# Portier.net
KiCad netlist of a schematic drawn in Altium Designer
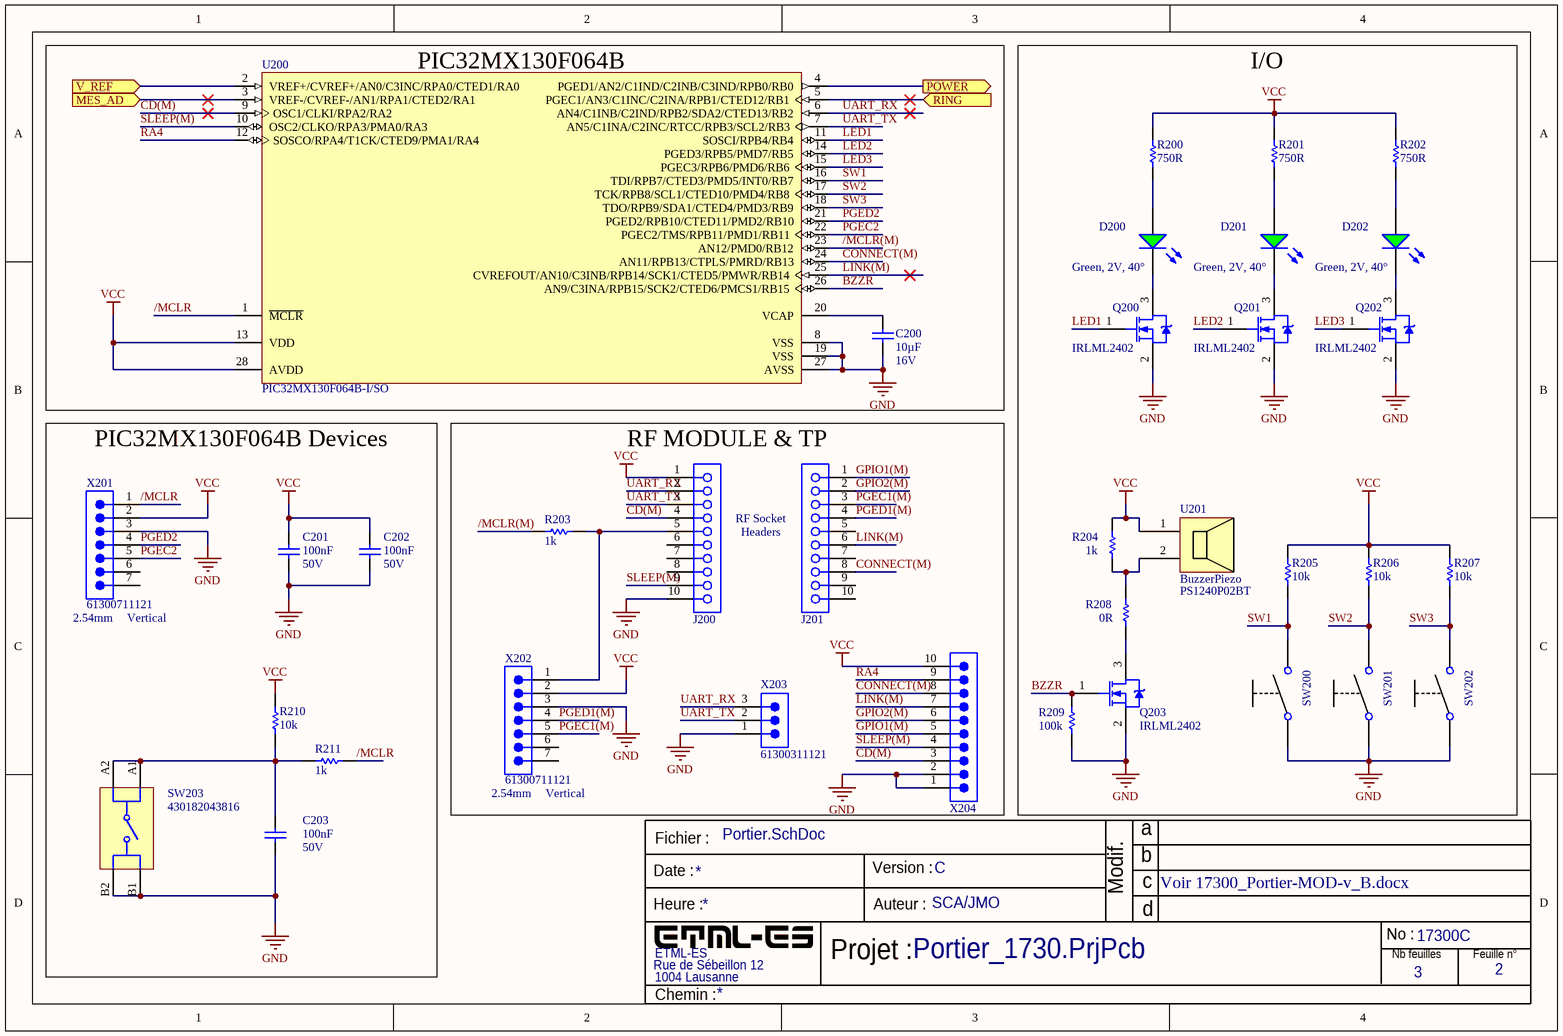
[diagram p0: Portier.SchDoc]

(export (version "E")
  (design (tool "Eeschema 10.0.6"))
  (components
    (comp (ref "C200")
      (value "10µF")
      (footprint "WCAP-CSGP_0805_L2W1.25H1.25")
      (description "WCAP-CSGP Multilayer Ceramic Chip Capacitor, General Purpose, size 0805, X5R, 10µF, 16VDC")
      (fields
        (field (name "MANUFACTURER PART NUMBER") "885012107014")
        (field (name "MANUFACTURER") "Wurth Elektronik")
        (field (name "RATED VOLTAGE (DC)") "16V")
      )
      (libsource (lib "Altium_WCAP-CSGP (rev22f)") (part "885012107014"))
    )
    (comp (ref "C201")
      (value "100nF")
      (footprint "WCAP-CSGP_0805_L2W1.25H0.8_Reflow")
      (description "WCAP-CSGP Multilayer Ceramic Chip Capacitor, General Purpose, size 0805, X7R, 100nF, 50VDC")
      (fields
        (field (name "MANUFACTURER") "Wurth Elektronik")
        (field (name "MANUFACTURER PART NUMBER") "885012207098")
        (field (name "RATED VOLTAGE (DC)") "50V")
      )
      (libsource (lib "Altium_WCAP-CSGP (rev22f)") (part "885012207098"))
    )
    (comp (ref "C202")
      (value "100nF")
      (footprint "WCAP-CSGP_0805_L2W1.25H0.8_Reflow")
      (description "WCAP-CSGP Multilayer Ceramic Chip Capacitor, General Purpose, size 0805, X7R, 100nF, 50VDC")
      (fields
        (field (name "MANUFACTURER") "Wurth Elektronik")
        (field (name "MANUFACTURER PART NUMBER") "885012207098")
        (field (name "RATED VOLTAGE (DC)") "50V")
      )
      (libsource (lib "Altium_WCAP-CSGP (rev22f)") (part "885012207098"))
    )
    (comp (ref "C203")
      (value "100nF")
      (footprint "WCAP-CSGP_0805_L2W1.25H0.8_Reflow")
      (description "WCAP-CSGP Multilayer Ceramic Chip Capacitor, General Purpose, size 0805, X7R, 100nF, 50VDC")
      (fields
        (field (name "MANUFACTURER") "Wurth Elektronik")
        (field (name "MANUFACTURER PART NUMBER") "885012207098")
        (field (name "RATED VOLTAGE (DC)") "50V")
      )
      (libsource (lib "Altium_WCAP-CSGP (rev22f)") (part "885012207098"))
    )
    (comp (ref "D200")
      (value "Green, 2V, 40°")
      (footprint "WL-SMCW_0805_150080xx75000")
      (description "WL-SMCW Mono-color Chip LED Waterclear, size 0805, Bright Green, 2V, 140°")
      (fields
        (field (name "MANUFACTURER PART NUMBER") "150080VS75000")
        (field (name "MANUFACTURER") "Wurth Elektronik")
      )
      (libsource (lib "Altium_WL-SMCW (rev22d)") (part "150080VS75000"))
    )
    (comp (ref "D201")
      (value "Green, 2V, 40°")
      (footprint "WL-SMCW_0805_150080xx75000")
      (description "WL-SMCW Mono-color Chip LED Waterclear, size 0805, Bright Green, 2V, 140°")
      (fields
        (field (name "MANUFACTURER PART NUMBER") "150080VS75000")
        (field (name "MANUFACTURER") "Wurth Elektronik")
      )
      (libsource (lib "Altium_WL-SMCW (rev22d)") (part "150080VS75000"))
    )
    (comp (ref "D202")
      (value "Green, 2V, 40°")
      (footprint "WL-SMCW_0805_150080xx75000")
      (description "WL-SMCW Mono-color Chip LED Waterclear, size 0805, Bright Green, 2V, 140°")
      (fields
        (field (name "MANUFACTURER PART NUMBER") "150080VS75000")
        (field (name "MANUFACTURER") "Wurth Elektronik")
      )
      (libsource (lib "Altium_WL-SMCW (rev22d)") (part "150080VS75000"))
    )
    (comp (ref "J200")
      (value "62001011821")
      (footprint "62001011821")
      (description "WR-PHD Socket Header, THT, Vertical, pitch 2mm, 1 Row, 10P")
      (fields (field (name "MANUFACTURER") "Wurth Elektronik"))
      (libsource (lib "Altium_WR-PHD (rev22b)") (part "62001011821"))
    )
    (comp (ref "J201")
      (value "62001011821")
      (footprint "62001011821")
      (description "WR-PHD Socket Header, THT, Vertical, pitch 2mm, 1 Row, 10P")
      (fields (field (name "MANUFACTURER") "Wurth Elektronik"))
      (libsource (lib "Altium_WR-PHD (rev22b)") (part "62001011821"))
    )
    (comp (ref "Q200")
      (value "IRLML2402")
      (footprint "INTR-IRLML2402TRPBF-3_V")
      (description "HEXFET(R) Power MOSFET, N-Channel, 20 V, 1.2 A, 3-Pin SOT-23, RoHS, Tape and Reel")
      (fields
        (field (name "MANUFACTURER") "Infineon Technologies")
        (field (name "PARTNUMBER") "IRLML2402TRBF")
      )
      (libsource (lib "Altium Content Vault") (part "CMP-2000-05155-1"))
    )
    (comp (ref "Q201")
      (value "IRLML2402")
      (footprint "INTR-IRLML2402TRPBF-3_V")
      (description "HEXFET(R) Power MOSFET, N-Channel, 20 V, 1.2 A, 3-Pin SOT-23, RoHS, Tape and Reel")
      (fields
        (field (name "MANUFACTURER") "Infineon Technologies")
        (field (name "PARTNUMBER") "IRLML2402TRBF")
      )
      (libsource (lib "Altium Content Vault") (part "CMP-2000-05155-1"))
    )
    (comp (ref "Q202")
      (value "IRLML2402")
      (footprint "INTR-IRLML2402TRPBF-3_V")
      (description "HEXFET(R) Power MOSFET, N-Channel, 20 V, 1.2 A, 3-Pin SOT-23, RoHS, Tape and Reel")
      (fields
        (field (name "MANUFACTURER") "Infineon Technologies")
        (field (name "PARTNUMBER") "IRLML2402TRBF")
      )
      (libsource (lib "Altium Content Vault") (part "CMP-2000-05155-1"))
    )
    (comp (ref "Q203")
      (value "IRLML2402")
      (footprint "INTR-IRLML2402TRPBF-3_V")
      (description "HEXFET(R) Power MOSFET, N-Channel, 20 V, 1.2 A, 3-Pin SOT-23, RoHS, Tape and Reel")
      (fields
        (field (name "MANUFACTURER") "Infineon Technologies")
        (field (name "PARTNUMBER") "IRLML2402TRBF")
      )
      (libsource (lib "Altium Content Vault") (part "CMP-2000-05155-1"))
    )
    (comp (ref "R200")
      (value "750R")
      (footprint "RESC2013X50X30NL20T20")
      (description "750 ohm, 0.125W, 1%., 0805")
      (fields (field (name "MANUFACTURER") "Vishay Dale") (field (name "PART NUMBER") "CRCW0805750KFKEA"))
      (libsource (lib "Altium Content Vault") (part "RES"))
    )
    (comp (ref "R201")
      (value "750R")
      (footprint "RESC2013X50X30NL20T20")
      (description "750 ohm, 0.125W, 1%., 0805")
      (fields (field (name "MANUFACTURER") "Vishay Dale") (field (name "PART NUMBER") "CRCW0805750KFKEA"))
      (libsource (lib "Altium Content Vault") (part "RES"))
    )
    (comp (ref "R202")
      (value "750R")
      (footprint "RESC2013X50X30NL20T20")
      (description "750 ohm, 0.125W, 1%., 0805")
      (fields (field (name "MANUFACTURER") "Vishay Dale") (field (name "PART NUMBER") "CRCW0805750KFKEA"))
      (libsource (lib "Altium Content Vault") (part "RES"))
    )
    (comp (ref "R203")
      (value "1k")
      (footprint "RESC2013X50X30ML20T20")
      (fields (field (name "PART NUMBER") "CRCW08051K00FKEA") (field (name "MANUFACTURER") "Vishay Dale"))
      (libsource (lib "Altium Content Vault") (part "RES"))
    )
    (comp (ref "R204")
      (value "1k")
      (footprint "RESC2013X50X30ML20T20")
      (fields (field (name "PART NUMBER") "CRCW08051K00FKEA") (field (name "MANUFACTURER") "Vishay Dale"))
      (libsource (lib "Altium Content Vault") (part "RES"))
    )
    (comp (ref "R205")
      (value "10k")
      (footprint "RESC2013X60X35NL10T20")
      (description "Chip Resistor, 10 KOhm, +/- 1%, 0.125 W, -55 to 155 degC, 0805 (2012 Metric), RoHS, Tape and Reel")
      (libsource (lib "Altium Content Vault") (part "RES-2"))
    )
    (comp (ref "R206")
      (value "10k")
      (footprint "RESC2013X60X35NL10T20")
      (description "Chip Resistor, 10 KOhm, +/- 1%, 0.125 W, -55 to 155 degC, 0805 (2012 Metric), RoHS, Tape and Reel")
      (libsource (lib "Altium Content Vault") (part "RES-2"))
    )
    (comp (ref "R207")
      (value "10k")
      (footprint "RESC2013X60X35NL10T20")
      (description "Chip Resistor, 10 KOhm, +/- 1%, 0.125 W, -55 to 155 degC, 0805 (2012 Metric), RoHS, Tape and Reel")
      (libsource (lib "Altium Content Vault") (part "RES-2"))
    )
    (comp (ref "R208")
      (value "0R")
      (footprint "RESC2013X60X35ML10T20")
      (description "Chip Resistor, 0 Ohm, +/- 5%, 125 mW, -55 to 155 degC, 0805 (2012 Metric), RoHS, Tape and Reel")
      (fields (field (name "MANUFACTURER") "Yageo"))
      (libsource (lib "Altium Content Vault") (part "RES-2"))
    )
    (comp (ref "R209")
      (value "100k")
      (footprint "RESC2013X70X40ML20T20")
      (description "100 kOhms ±1% 0.125W, 1/8W Chip Resistor 0805 (2012 Metric) Automotive AEC-Q200 Thick Film")
      (fields (field (name "PART NUMBER") "ERJ-6ENF1003V") (field (name "MANUFACTURER") "Panasonic"))
      (libsource (lib "Altium Content Vault") (part "RES"))
    )
    (comp (ref "R210")
      (value "10k")
      (footprint "RESC2013X60X35NL10T20")
      (description "Chip Resistor, 10 KOhm, +/- 1%, 0.125 W, -55 to 155 degC, 0805 (2012 Metric), RoHS, Tape and Reel")
      (libsource (lib "Altium Content Vault") (part "RES-2"))
    )
    (comp (ref "R211")
      (value "1k")
      (footprint "RESC2013X50X30ML20T20")
      (fields (field (name "PART NUMBER") "CRCW08051K00FKEA") (field (name "MANUFACTURER") "Vishay Dale"))
      (libsource (lib "Altium Content Vault") (part "RES"))
    )
    (comp (ref "SW200")
      (value "Tact-sw 1241.1022")
      (footprint "Tact-sw 1241.1022")
      (libsource (lib "Schurter-switches") (part "Tact-sw 1241.1022"))
    )
    (comp (ref "SW201")
      (value "Tact-sw 1241.1022")
      (footprint "Tact-sw 1241.1022")
      (libsource (lib "Schurter-switches") (part "Tact-sw 1241.1022"))
    )
    (comp (ref "SW202")
      (value "Tact-sw 1241.1022")
      (footprint "Tact-sw 1241.1022")
      (libsource (lib "Schurter-switches") (part "Tact-sw 1241.1022"))
    )
    (comp (ref "SW203")
      (value "430182043816")
      (footprint "WS-TASV_L6W6H4.3_4301x20438x6")
      (description "WS-TASV SMT Tact Switch, L6 x W6 x H4.3mm, 160g, SPST-NO, 12V, 50mA")
      (fields (field (name "MANUFACTURER") "Wurth Elektronik"))
      (libsource (lib "Altium_WS-TASV (rev22c)") (part "430182043816"))
    )
    (comp (ref "U200")
      (value "PIC32MX130F064B-I/SO")
      (footprint "MCHP-SOIC-SO28_M")
      (fields (field (name "MANUFACTURER") "Microchip"))
      (libsource (lib "Altium Content Vault") (part "MCHP-PIC32MX1X0FXXXB-28"))
    )
    (comp (ref "U201")
      (value "BuzzerPiezo")
      (footprint "Buzzer")
      (description "Buzzer 12mm piezo")
      (fields
        (field (name "MANUFACTURER") "TDK Corporation")
        (field (name "PARTNUMBER") "PS1240P02BT")
        (field (name "ALTIUM_VALUE") "PS1240P02BT")
      )
      (libsource (lib "CircuitOUT") (part "BZR"))
    )
    (comp (ref "X201")
      (value "61300711121")
      (footprint "61300711121")
      (description "WR-PHD Pin Header, THT, Vertical, pitch 2.54mm, 1 Row, 7P")
      (fields
        (field (name "MANUFACTURER") "Wurth Elektronik")
        (field (name "ORIENTATION") "Vertical")
        (field (name "PITCH") "2.54mm")
      )
      (libsource (lib "Altium_WR-PHD (rev22b)") (part "61300711121"))
    )
    (comp (ref "X202")
      (value "61300711121")
      (footprint "61300711121")
      (description "WR-PHD Pin Header, THT, Vertical, pitch 2.54mm, 1 Row, 7P")
      (fields
        (field (name "MANUFACTURER") "Wurth Elektronik")
        (field (name "ORIENTATION") "Vertical")
        (field (name "PITCH") "2.54mm")
      )
      (libsource (lib "Altium_WR-PHD (rev22b)") (part "61300711121"))
    )
    (comp (ref "X203")
      (value "61300311121")
      (footprint "61300311121")
      (description "WR-PHD Pin Header, THT, Vertical, pitch 2.54mm, 1 Row, 3P")
      (fields (field (name "MANUFACTURER") "Wurth Elektronik"))
      (libsource (lib "Altium_WR-PHD (rev22b)") (part "61300311121"))
    )
    (comp (ref "X204")
      (value "61301011121")
      (footprint "61301011121")
      (description "WR-PHD Pin Header, THT, Vertical, pitch 2.54mm, 1 Row, 10P")
      (fields (field (name "MANUFACTURER") "Wurth Elektronik"))
      (libsource (lib "Altium_WR-PHD (rev22b)") (part "61301011121"))
    )
  )
  (nets
    (net (code "1") (name "/BZZR") (class "Default")
      (node (ref "Q203") (pin "1") (pinfunction "G_1") (pintype "passive"))
      (node (ref "R209") (pin "2") (pinfunction "2_2") (pintype "passive"))
      (node (ref "U200") (pin "26") (pinfunction "AN9/C3INA/RPB15/SCK2/CTED6/PMCS1/RB15_26") (pintype "bidirectional"))
    )
    (net (code "2") (name "/CD(M)") (class "Default")
      (node (ref "J200") (pin "4") (pinfunction "4_4") (pintype "passive"))
      (node (ref "U200") (pin "9") (pinfunction "OSC1/CLKI/RPA2/RA2_9") (pintype "input"))
      (node (ref "X204") (pin "3") (pinfunction "3_3") (pintype "passive"))
    )
    (net (code "3") (name "/CONNECT(M)") (class "Default")
      (node (ref "J201") (pin "8") (pinfunction "8_8") (pintype "passive"))
      (node (ref "U200") (pin "24") (pinfunction "AN11/RPB13/CTPLS/PMRD/RB13_24") (pintype "bidirectional"))
      (node (ref "X204") (pin "8") (pinfunction "8_8") (pintype "passive"))
    )
    (net (code "4") (name "/GPIO1(M)") (class "Default")
      (node (ref "J201") (pin "1") (pinfunction "1_1") (pintype "passive"))
      (node (ref "X204") (pin "5") (pinfunction "5_5") (pintype "passive"))
    )
    (net (code "5") (name "/GPIO2(M)") (class "Default")
      (node (ref "J201") (pin "2") (pinfunction "2_2") (pintype "passive"))
      (node (ref "X204") (pin "6") (pinfunction "6_6") (pintype "passive"))
    )
    (net (code "6") (name "/LED1") (class "Default")
      (node (ref "Q200") (pin "1") (pinfunction "G_1") (pintype "passive"))
      (node (ref "U200") (pin "11") (pinfunction "SOSCI/RPB4/RB4_11") (pintype "bidirectional"))
    )
    (net (code "7") (name "/LED2") (class "Default")
      (node (ref "Q201") (pin "1") (pinfunction "G_1") (pintype "passive"))
      (node (ref "U200") (pin "14") (pinfunction "PGED3/RPB5/PMD7/RB5_14") (pintype "bidirectional"))
    )
    (net (code "8") (name "/LED3") (class "Default")
      (node (ref "Q202") (pin "1") (pinfunction "G_1") (pintype "passive"))
      (node (ref "U200") (pin "15") (pinfunction "PGEC3/RPB6/PMD6/RB6_15") (pintype "bidirectional"))
    )
    (net (code "9") (name "/LINK(M)") (class "Default")
      (node (ref "J201") (pin "6") (pinfunction "6_6") (pintype "passive"))
      (node (ref "U200") (pin "25") (pinfunction "CVREFOUT/AN10/C3INB/RPB14/SCK1/CTED5/PMWR/RB14_25") (pintype "input"))
      (node (ref "X204") (pin "7") (pinfunction "7_7") (pintype "passive"))
    )
    (net (code "10") (name "/MES_AD") (class "Default")
      (node (ref "U200") (pin "3") (pinfunction "VREF-/CVREF-/AN1/RPA1/CTED2/RA1_3") (pintype "input"))
    )
    (net (code "11") (name "/PGEC1(M)") (class "Default")
      (node (ref "J201") (pin "3") (pinfunction "3_3") (pintype "passive"))
      (node (ref "X202") (pin "5") (pinfunction "5_5") (pintype "passive"))
    )
    (net (code "12") (name "/PGEC2") (class "Default")
      (node (ref "U200") (pin "22") (pinfunction "PGEC2/TMS/RPB11/PMD1/RB11_22") (pintype "bidirectional"))
      (node (ref "X201") (pin "5") (pinfunction "5_5") (pintype "passive"))
    )
    (net (code "13") (name "/PGED1(M)") (class "Default")
      (node (ref "J201") (pin "4") (pinfunction "4_4") (pintype "passive"))
      (node (ref "X202") (pin "4") (pinfunction "4_4") (pintype "passive"))
    )
    (net (code "14") (name "/PGED2") (class "Default")
      (node (ref "U200") (pin "21") (pinfunction "PGED2/RPB10/CTED11/PMD2/RB10_21") (pintype "bidirectional"))
      (node (ref "X201") (pin "4") (pinfunction "4_4") (pintype "passive"))
    )
    (net (code "15") (name "/POWER") (class "Default")
      (node (ref "U200") (pin "4") (pinfunction "PGED1/AN2/C1IND/C2INB/C3IND/RPB0/RB0_4") (pintype "output"))
    )
    (net (code "16") (name "/RA4") (class "Default")
      (node (ref "U200") (pin "12") (pinfunction "SOSCO/RPA4/T1CK/CTED9/PMA1/RA4_12") (pintype "bidirectional"))
      (node (ref "X204") (pin "9") (pinfunction "9_9") (pintype "passive"))
    )
    (net (code "17") (name "/RING") (class "Default")
      (node (ref "U200") (pin "5") (pinfunction "PGEC1/AN3/C1INC/C2INA/RPB1/CTED12/RB1_5") (pintype "input"))
    )
    (net (code "18") (name "/SLEEP(M)") (class "Default")
      (node (ref "J200") (pin "9") (pinfunction "9_9") (pintype "passive"))
      (node (ref "U200") (pin "10") (pinfunction "OSC2/CLKO/RPA3/PMA0/RA3_10") (pintype "bidirectional"))
      (node (ref "X204") (pin "4") (pinfunction "4_4") (pintype "passive"))
    )
    (net (code "19") (name "/SW1") (class "Default")
      (node (ref "R205") (pin "1") (pinfunction "1_1") (pintype "passive"))
      (node (ref "SW200") (pin "2") (pinfunction "2_2") (pintype "passive"))
      (node (ref "U200") (pin "16") (pinfunction "TDI/RPB7/CTED3/PMD5/INT0/RB7_16") (pintype "bidirectional"))
    )
    (net (code "20") (name "/SW2") (class "Default")
      (node (ref "R206") (pin "1") (pinfunction "1_1") (pintype "passive"))
      (node (ref "SW201") (pin "2") (pinfunction "2_2") (pintype "passive"))
      (node (ref "U200") (pin "17") (pinfunction "TCK/RPB8/SCL1/CTED10/PMD4/RB8_17") (pintype "bidirectional"))
    )
    (net (code "21") (name "/SW3") (class "Default")
      (node (ref "R207") (pin "1") (pinfunction "1_1") (pintype "passive"))
      (node (ref "SW202") (pin "2") (pinfunction "2_2") (pintype "passive"))
      (node (ref "U200") (pin "18") (pinfunction "TDO/RPB9/SDA1/CTED4/PMD3/RB9_18") (pintype "bidirectional"))
    )
    (net (code "22") (name "/UART_RX") (class "Default")
      (node (ref "J200") (pin "2") (pinfunction "2_2") (pintype "passive"))
      (node (ref "U200") (pin "6") (pinfunction "AN4/C1INB/C2IND/RPB2/SDA2/CTED13/RB2_6") (pintype "input"))
      (node (ref "X203") (pin "3") (pinfunction "3_3") (pintype "passive"))
    )
    (net (code "23") (name "/UART_TX") (class "Default")
      (node (ref "J200") (pin "3") (pinfunction "3_3") (pintype "passive"))
      (node (ref "U200") (pin "7") (pinfunction "AN5/C1INA/C2INC/RTCC/RPB3/SCL2/RB3_7") (pintype "output"))
      (node (ref "X203") (pin "2") (pinfunction "2_2") (pintype "passive"))
    )
    (net (code "24") (name "/V_REF") (class "Default")
      (node (ref "U200") (pin "2") (pinfunction "VREF+/CVREF+/AN0/C3INC/RPA0/CTED1/RA0_2") (pintype "input"))
    )
    (net (code "25") (name "/{slash}MCLR") (class "Default")
      (node (ref "R211") (pin "2") (pinfunction "2_2") (pintype "passive"))
      (node (ref "U200") (pin "1") (pinfunction "~{MCLR}_1") (pintype "passive"))
      (node (ref "X201") (pin "1") (pinfunction "1_1") (pintype "passive"))
    )
    (net (code "26") (name "/{slash}MCLR(M)") (class "Default")
      (node (ref "R203") (pin "2") (pinfunction "2_2") (pintype "passive"))
      (node (ref "U200") (pin "23") (pinfunction "AN12/PMD0/RB12_23") (pintype "bidirectional"))
    )
    (net (code "27") (name "GND") (class "Default")
      (node (ref "C200") (pin "2") (pinfunction "2_2") (pintype "passive"))
      (node (ref "C201") (pin "1") (pinfunction "1_1") (pintype "passive"))
      (node (ref "C202") (pin "1") (pinfunction "1_1") (pintype "passive"))
      (node (ref "C203") (pin "1") (pinfunction "1_1") (pintype "passive"))
      (node (ref "J200") (pin "10") (pinfunction "10_10") (pintype "passive"))
      (node (ref "Q200") (pin "2") (pinfunction "S_2") (pintype "passive"))
      (node (ref "Q201") (pin "2") (pinfunction "S_2") (pintype "passive"))
      (node (ref "Q202") (pin "2") (pinfunction "S_2") (pintype "passive"))
      (node (ref "Q203") (pin "2") (pinfunction "S_2") (pintype "passive"))
      (node (ref "R209") (pin "1") (pinfunction "1_1") (pintype "passive"))
      (node (ref "SW200") (pin "1") (pinfunction "1_1") (pintype "passive"))
      (node (ref "SW201") (pin "1") (pinfunction "1_1") (pintype "passive"))
      (node (ref "SW202") (pin "1") (pinfunction "1_1") (pintype "passive"))
      (node (ref "SW203") (pin "B1") (pinfunction "B1_B1") (pintype "passive"))
      (node (ref "SW203") (pin "B2") (pinfunction "B2_B2") (pintype "passive"))
      (node (ref "U200") (pin "19") (pinfunction "VSS_19") (pintype "power_in"))
      (node (ref "U200") (pin "27") (pinfunction "AVSS_27") (pintype "power_in"))
      (node (ref "U200") (pin "8") (pinfunction "VSS_8") (pintype "power_in"))
      (node (ref "X201") (pin "3") (pinfunction "3_3") (pintype "passive"))
      (node (ref "X202") (pin "3") (pinfunction "3_3") (pintype "passive"))
      (node (ref "X203") (pin "1") (pinfunction "1_1") (pintype "passive"))
      (node (ref "X204") (pin "1") (pinfunction "1_1") (pintype "passive"))
      (node (ref "X204") (pin "2") (pinfunction "2_2") (pintype "passive"))
    )
    (net (code "28") (name "Net-(C203-Pad2)") (class "Default")
      (node (ref "C203") (pin "2") (pinfunction "2_2") (pintype "passive"))
      (node (ref "R210") (pin "2") (pinfunction "2_2") (pintype "passive"))
      (node (ref "R211") (pin "1") (pinfunction "1_1") (pintype "passive"))
      (node (ref "SW203") (pin "A1") (pinfunction "A1_A1") (pintype "passive"))
      (node (ref "SW203") (pin "A2") (pinfunction "A2_A2") (pintype "passive"))
    )
    (net (code "29") (name "Net-(D200-A)") (class "Default")
      (node (ref "D200") (pin "2") (pinfunction "A_2") (pintype "passive"))
      (node (ref "R200") (pin "2") (pinfunction "2_2") (pintype "passive"))
    )
    (net (code "30") (name "Net-(D200-K)") (class "Default")
      (node (ref "D200") (pin "1") (pinfunction "K_1") (pintype "passive"))
      (node (ref "Q200") (pin "3") (pinfunction "D_3") (pintype "passive"))
    )
    (net (code "31") (name "Net-(D201-A)") (class "Default")
      (node (ref "D201") (pin "2") (pinfunction "A_2") (pintype "passive"))
      (node (ref "R201") (pin "2") (pinfunction "2_2") (pintype "passive"))
    )
    (net (code "32") (name "Net-(D201-K)") (class "Default")
      (node (ref "D201") (pin "1") (pinfunction "K_1") (pintype "passive"))
      (node (ref "Q201") (pin "3") (pinfunction "D_3") (pintype "passive"))
    )
    (net (code "33") (name "Net-(D202-A)") (class "Default")
      (node (ref "D202") (pin "2") (pinfunction "A_2") (pintype "passive"))
      (node (ref "R202") (pin "1") (pinfunction "1_1") (pintype "passive"))
    )
    (net (code "34") (name "Net-(D202-K)") (class "Default")
      (node (ref "D202") (pin "1") (pinfunction "K_1") (pintype "passive"))
      (node (ref "Q202") (pin "3") (pinfunction "D_3") (pintype "passive"))
    )
    (net (code "35") (name "Net-(J200-Pad5)") (class "Default")
      (node (ref "J200") (pin "5") (pinfunction "5_5") (pintype "passive"))
      (node (ref "R203") (pin "1") (pinfunction "1_1") (pintype "passive"))
      (node (ref "X202") (pin "1") (pinfunction "1_1") (pintype "passive"))
    )
    (net (code "36") (name "Net-(Q203-D)") (class "Default")
      (node (ref "Q203") (pin "3") (pinfunction "D_3") (pintype "passive"))
      (node (ref "R208") (pin "1") (pinfunction "1_1") (pintype "passive"))
    )
    (net (code "37") (name "Net-(R204-Pad1)") (class "Default")
      (node (ref "R204") (pin "1") (pinfunction "1_1") (pintype "passive"))
      (node (ref "R208") (pin "2") (pinfunction "2_2") (pintype "passive"))
      (node (ref "U201") (pin "2") (pintype "passive"))
    )
    (net (code "38") (name "Net-(U200-VCAP)") (class "Default")
      (node (ref "C200") (pin "1") (pinfunction "1_1") (pintype "passive"))
      (node (ref "U200") (pin "20") (pinfunction "VCAP_20") (pintype "passive"))
    )
    (net (code "39") (name "VCC") (class "Default")
      (node (ref "C201") (pin "2") (pinfunction "2_2") (pintype "passive"))
      (node (ref "C202") (pin "2") (pinfunction "2_2") (pintype "passive"))
      (node (ref "J200") (pin "1") (pinfunction "1_1") (pintype "passive"))
      (node (ref "R200") (pin "1") (pinfunction "1_1") (pintype "passive"))
      (node (ref "R201") (pin "1") (pinfunction "1_1") (pintype "passive"))
      (node (ref "R202") (pin "2") (pinfunction "2_2") (pintype "passive"))
      (node (ref "R204") (pin "2") (pinfunction "2_2") (pintype "passive"))
      (node (ref "R205") (pin "2") (pinfunction "2_2") (pintype "passive"))
      (node (ref "R206") (pin "2") (pinfunction "2_2") (pintype "passive"))
      (node (ref "R207") (pin "2") (pinfunction "2_2") (pintype "passive"))
      (node (ref "R210") (pin "1") (pinfunction "1_1") (pintype "passive"))
      (node (ref "U200") (pin "13") (pinfunction "VDD_13") (pintype "power_in"))
      (node (ref "U200") (pin "28") (pinfunction "AVDD_28") (pintype "power_in"))
      (node (ref "U201") (pin "1") (pintype "passive"))
      (node (ref "X201") (pin "2") (pinfunction "2_2") (pintype "passive"))
      (node (ref "X202") (pin "2") (pinfunction "2_2") (pintype "passive"))
      (node (ref "X204") (pin "10") (pinfunction "10_10") (pintype "passive"))
    )
    (net (code "40") (name "unconnected-(J200-Pad6)") (class "Default")
      (node (ref "J200") (pin "6") (pinfunction "6_6") (pintype "passive"))
    )
    (net (code "41") (name "unconnected-(J200-Pad7)") (class "Default")
      (node (ref "J200") (pin "7") (pinfunction "7_7") (pintype "passive"))
    )
    (net (code "42") (name "unconnected-(J200-Pad8)") (class "Default")
      (node (ref "J200") (pin "8") (pinfunction "8_8") (pintype "passive"))
    )
    (net (code "43") (name "unconnected-(J201-Pad5)") (class "Default")
      (node (ref "J201") (pin "5") (pinfunction "5_5") (pintype "passive"))
    )
    (net (code "44") (name "unconnected-(J201-Pad7)") (class "Default")
      (node (ref "J201") (pin "7") (pinfunction "7_7") (pintype "passive"))
    )
    (net (code "45") (name "unconnected-(J201-Pad9)") (class "Default")
      (node (ref "J201") (pin "9") (pinfunction "9_9") (pintype "passive"))
    )
    (net (code "46") (name "unconnected-(J201-Pad10)") (class "Default")
      (node (ref "J201") (pin "10") (pinfunction "10_10") (pintype "passive"))
    )
    (net (code "47") (name "unconnected-(X201-Pad6)") (class "Default")
      (node (ref "X201") (pin "6") (pinfunction "6_6") (pintype "passive"))
    )
    (net (code "48") (name "unconnected-(X201-Pad7)") (class "Default")
      (node (ref "X201") (pin "7") (pinfunction "7_7") (pintype "passive"))
    )
    (net (code "49") (name "unconnected-(X202-Pad6)") (class "Default")
      (node (ref "X202") (pin "6") (pinfunction "6_6") (pintype "passive"))
    )
    (net (code "50") (name "unconnected-(X202-Pad7)") (class "Default")
      (node (ref "X202") (pin "7") (pinfunction "7_7") (pintype "passive"))
    )
  )
)
